# Transistors.net
KiCad netlist of a schematic drawn in Altium Designer
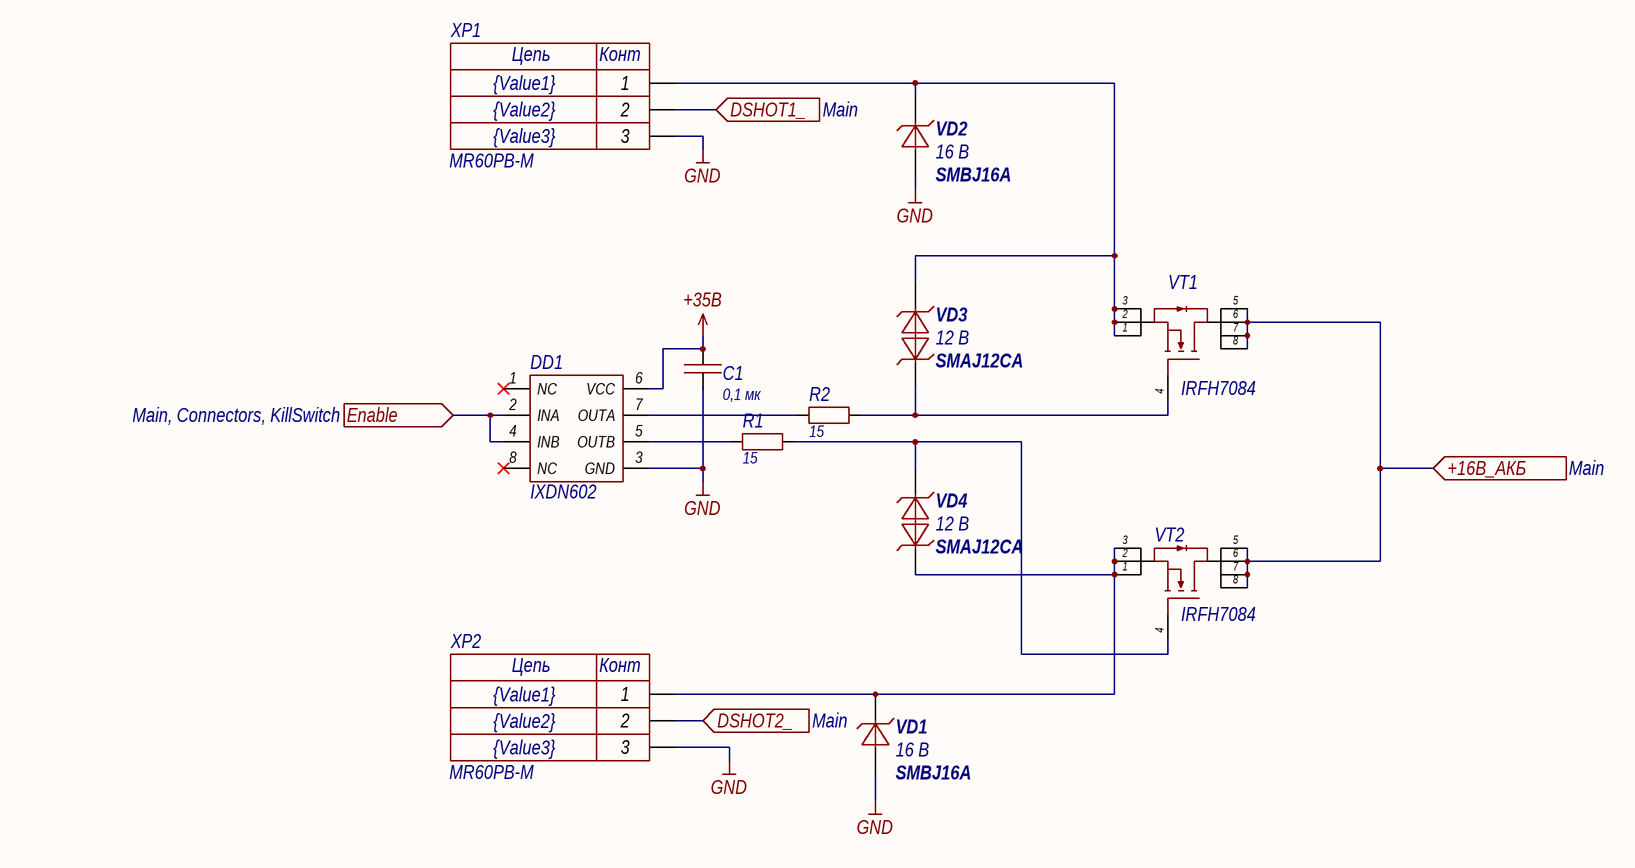
[diagram p0: Transistors.SchDoc]

(export (version "E")
  (design (tool "Eeschema 10.0.6"))
  (components
    (comp (ref "C1")
      (value "0,1 мк")
      (footprint "0603C")
      (description "Конденсатор")
      (fields (field (name "PART NUMBER") "Capacitor_0,1u_10_50V_X7R_0603C") (field (name "TOLERANCE") "0,1"))
      (libsource (lib "Hydrolib") (part "Capacitor"))
    )
    (comp (ref "DD1")
      (value "IXDN602")
      (footprint "SOIC-8")
      (description "Двухканальный драйвер затвора для mosfet и igbt транзисторов")
      (libsource (lib "Hydrolib") (part "IXDN602"))
    )
    (comp (ref "R1")
      (value "15")
      (footprint "0603R")
      (description "Резистор номиналом 15 Ом 1%")
      (fields (field (name "PART NUMBER") "Resistor_15_1_0603") (field (name "TOLERANCE") "1%"))
      (libsource (lib "Hydrolib") (part "Resistor"))
    )
    (comp (ref "R2")
      (value "15")
      (footprint "0603R")
      (description "Резистор номиналом 15 Ом 1%")
      (fields (field (name "PART NUMBER") "Resistor_15_1_0603") (field (name "TOLERANCE") "1%"))
      (libsource (lib "Hydrolib") (part "Resistor"))
    )
    (comp (ref "VD1")
      (value "SMBJ16A")
      (footprint "SMB")
      (description "Защитный диод на 16 В, рассеиваемая мощность 600 Вт")
      (fields (field (name "ALTIUM_VALUE") "16 В"))
      (libsource (lib "Hydrolib") (part "TVS_1_1dir"))
    )
    (comp (ref "VD2")
      (value "SMBJ16A")
      (footprint "SMB")
      (description "Защитный диод на 16 В, рассеиваемая мощность 600 Вт")
      (fields (field (name "ALTIUM_VALUE") "16 В"))
      (libsource (lib "Hydrolib") (part "TVS_1_1dir"))
    )
    (comp (ref "VD3")
      (value "SMAJ12CA")
      (footprint "SMA")
      (description "Защитный диод на 12 В, рассеиваемая мощность 400 Вт")
      (fields (field (name "ALTIUM_VALUE") "12 В"))
      (libsource (lib "Hydrolib") (part "TVS_1_2dir"))
    )
    (comp (ref "VD4")
      (value "SMAJ12CA")
      (footprint "SMA")
      (description "Защитный диод на 12 В, рассеиваемая мощность 400 Вт")
      (fields (field (name "ALTIUM_VALUE") "12 В"))
      (libsource (lib "Hydrolib") (part "TVS_1_2dir"))
    )
    (comp (ref "VT1")
      (value "IRFH7084")
      (footprint "PQFN_5x6")
      (description "N-канальный MOSFET")
      (libsource (lib "Hydrolib") (part "MOSFET_N-channel_8pin"))
    )
    (comp (ref "VT2")
      (value "IRFH7084")
      (footprint "PQFN_5x6")
      (description "N-канальный MOSFET")
      (libsource (lib "Hydrolib") (part "MOSFET_N-channel_8pin"))
    )
    (comp (ref "XP1")
      (value "MR60PB-M")
      (footprint "MR60PB-M")
      (description "60 А (40 продолжительно), 3 контакта, прямой отец")
      (fields
        (field (name "VALUE3") "{Value3}")
        (field (name "VALUE2") "{Value2}")
        (field (name "VALUE1") "{Value1}")
      )
      (libsource (lib "Hydrolib") (part "Conn_3pin"))
    )
    (comp (ref "XP2")
      (value "MR60PB-M")
      (footprint "MR60PB-M")
      (description "60 А (40 продолжительно), 3 контакта, прямой отец")
      (fields
        (field (name "VALUE3") "{Value3}")
        (field (name "VALUE2") "{Value2}")
        (field (name "VALUE1") "{Value1}")
      )
      (libsource (lib "Hydrolib") (part "Conn_3pin"))
    )
  )
  (nets
    (net (code "1") (name "+35В") (class "Default")
      (node (ref "C1") (pin "2") (pinfunction "2_2") (pintype "passive"))
      (node (ref "DD1") (pin "6") (pinfunction "VCC_6") (pintype "passive"))
    )
    (net (code "2") (name "/+16В_АКБ") (class "Default")
      (node (ref "VT1") (pin "5") (pinfunction "5_5") (pintype "passive"))
      (node (ref "VT1") (pin "6") (pinfunction "6_6") (pintype "passive"))
      (node (ref "VT1") (pin "7") (pinfunction "7_7") (pintype "passive"))
      (node (ref "VT1") (pin "8") (pinfunction "8_8") (pintype "passive"))
      (node (ref "VT2") (pin "5") (pinfunction "5_5") (pintype "passive"))
      (node (ref "VT2") (pin "6") (pinfunction "6_6") (pintype "passive"))
      (node (ref "VT2") (pin "7") (pinfunction "7_7") (pintype "passive"))
      (node (ref "VT2") (pin "8") (pinfunction "8_8") (pintype "passive"))
    )
    (net (code "3") (name "/DSHOT1_") (class "Default")
      (node (ref "XP1") (pin "2") (pinfunction "2_2") (pintype "passive"))
    )
    (net (code "4") (name "/DSHOT2_") (class "Default")
      (node (ref "XP2") (pin "2") (pinfunction "2_2") (pintype "passive"))
    )
    (net (code "5") (name "/Enable") (class "Default")
      (node (ref "DD1") (pin "2") (pinfunction "INA_2") (pintype "passive"))
      (node (ref "DD1") (pin "4") (pinfunction "INB_4") (pintype "passive"))
    )
    (net (code "6") (name "GND") (class "Default")
      (node (ref "C1") (pin "1") (pinfunction "1_1") (pintype "passive"))
      (node (ref "DD1") (pin "3") (pinfunction "GND_3") (pintype "passive"))
      (node (ref "VD1") (pin "1") (pinfunction "1_1") (pintype "passive"))
      (node (ref "VD2") (pin "1") (pinfunction "1_1") (pintype "passive"))
      (node (ref "XP1") (pin "3") (pinfunction "3_3") (pintype "passive"))
      (node (ref "XP2") (pin "3") (pinfunction "3_3") (pintype "passive"))
    )
    (net (code "7") (name "Net-(DD1-OUTA)") (class "Default")
      (node (ref "DD1") (pin "7") (pinfunction "OUTA_7") (pintype "passive"))
      (node (ref "R2") (pin "1") (pinfunction "1_1") (pintype "passive"))
    )
    (net (code "8") (name "Net-(DD1-OUTB)") (class "Default")
      (node (ref "DD1") (pin "5") (pinfunction "OUTB_5") (pintype "passive"))
      (node (ref "R1") (pin "1") (pinfunction "1_1") (pintype "passive"))
    )
    (net (code "9") (name "Net-(R1-Pad2)") (class "Default")
      (node (ref "R1") (pin "2") (pinfunction "2_2") (pintype "passive"))
      (node (ref "VD4") (pin "2") (pinfunction "2_2") (pintype "passive"))
      (node (ref "VT2") (pin "4") (pinfunction "4_4") (pintype "passive"))
    )
    (net (code "10") (name "Net-(R2-Pad2)") (class "Default")
      (node (ref "R2") (pin "2") (pinfunction "2_2") (pintype "passive"))
      (node (ref "VD3") (pin "1") (pinfunction "1_1") (pintype "passive"))
      (node (ref "VT1") (pin "4") (pinfunction "4_4") (pintype "passive"))
    )
    (net (code "11") (name "Net-(VD1-Pad2)") (class "Default")
      (node (ref "VD1") (pin "2") (pinfunction "2_2") (pintype "passive"))
      (node (ref "VD4") (pin "1") (pinfunction "1_1") (pintype "passive"))
      (node (ref "VT2") (pin "1") (pinfunction "1_1") (pintype "passive"))
      (node (ref "VT2") (pin "2") (pinfunction "2_2") (pintype "passive"))
      (node (ref "VT2") (pin "3") (pinfunction "3_3") (pintype "passive"))
      (node (ref "XP2") (pin "1") (pinfunction "1_1") (pintype "passive"))
    )
    (net (code "12") (name "Net-(VD2-Pad2)") (class "Default")
      (node (ref "VD2") (pin "2") (pinfunction "2_2") (pintype "passive"))
      (node (ref "VD3") (pin "2") (pinfunction "2_2") (pintype "passive"))
      (node (ref "VT1") (pin "1") (pinfunction "1_1") (pintype "passive"))
      (node (ref "VT1") (pin "2") (pinfunction "2_2") (pintype "passive"))
      (node (ref "VT1") (pin "3") (pinfunction "3_3") (pintype "passive"))
      (node (ref "XP1") (pin "1") (pinfunction "1_1") (pintype "passive"))
    )
    (net (code "13") (name "unconnected-(DD1-NC-Pad1)") (class "Default")
      (node (ref "DD1") (pin "1") (pinfunction "NC_1") (pintype "passive+no_connect"))
    )
    (net (code "14") (name "unconnected-(DD1-NC-Pad8)") (class "Default")
      (node (ref "DD1") (pin "8") (pinfunction "NC_8") (pintype "passive+no_connect"))
    )
  )
)
